# OpticalFlowExt.net
KiCad netlist of a schematic drawn in Altium Designer
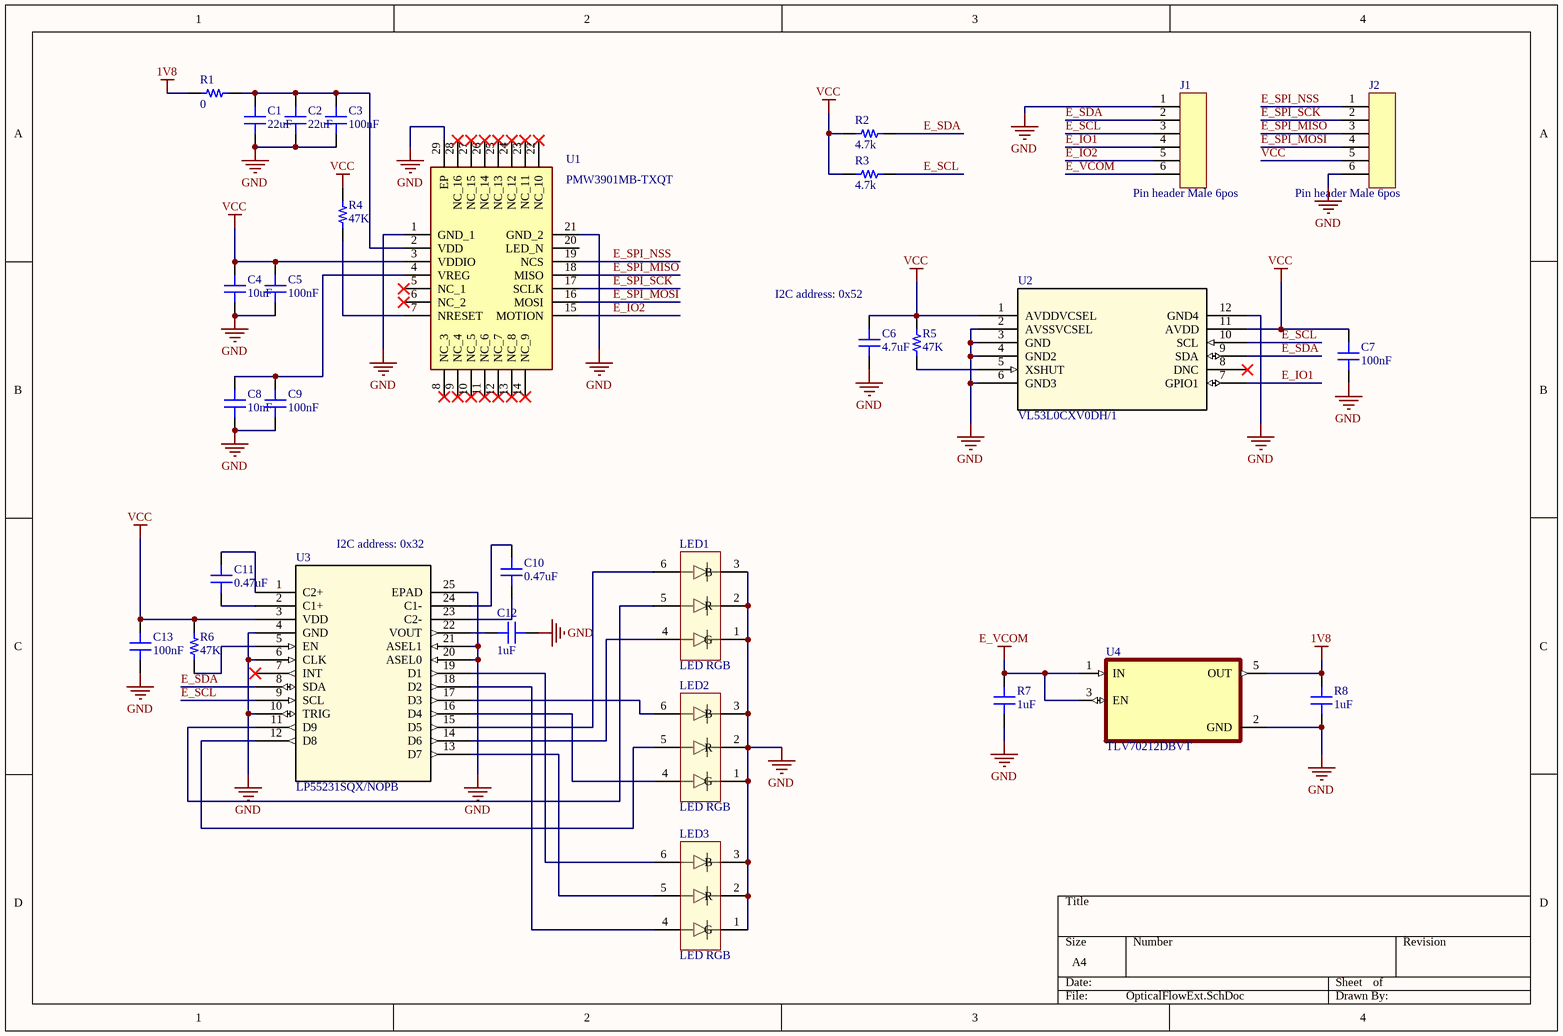
[diagram p0: OpticalFlowExt.SchDoc]

(export (version "E")
  (design (tool "Eeschema 10.0.6"))
  (components
    (comp (ref "C1")
      (value "22uF")
      (footprint "CAP 0402_1005")
      (description "CAP CER 150PF 50V NP0 0402")
      (fields (field (name "PART NUMBER") "C0402C151F5GAC7867") (field (name "MANUFACTURER") "KEMET"))
      (libsource (lib "Celestial Altium Library - altium_library") (part "Capacitor"))
    )
    (comp (ref "C2")
      (value "22uF")
      (footprint "CAP 0402_1005")
      (description "CAP CER 150PF 50V NP0 0402")
      (fields (field (name "PART NUMBER") "C0402C151F5GAC7867") (field (name "MANUFACTURER") "KEMET"))
      (libsource (lib "Celestial Altium Library - altium_library") (part "Capacitor"))
    )
    (comp (ref "C3")
      (value "100nF")
      (footprint "CAP 0402_1005")
      (description "CAP CER 150PF 50V NP0 0402")
      (fields (field (name "PART NUMBER") "C0402C151F5GAC7867") (field (name "MANUFACTURER") "KEMET"))
      (libsource (lib "Celestial Altium Library - altium_library") (part "Capacitor"))
    )
    (comp (ref "C4")
      (value "10uF")
      (footprint "CAP 0402_1005")
      (description "CAP CER 150PF 50V NP0 0402")
      (fields (field (name "PART NUMBER") "C0402C151F5GAC7867") (field (name "MANUFACTURER") "KEMET"))
      (libsource (lib "Celestial Altium Library - altium_library") (part "Capacitor"))
    )
    (comp (ref "C5")
      (value "100nF")
      (footprint "CAP 0402_1005")
      (description "CAP CER 150PF 50V NP0 0402")
      (fields (field (name "PART NUMBER") "C0402C151F5GAC7867") (field (name "MANUFACTURER") "KEMET"))
      (libsource (lib "Celestial Altium Library - altium_library") (part "Capacitor"))
    )
    (comp (ref "C6")
      (value "4.7uF")
      (footprint "CAP 0402_1005")
      (description "CAP CER 150PF 50V NP0 0402")
      (fields (field (name "PART NUMBER") "C0402C151F5GAC7867") (field (name "MANUFACTURER") "KEMET"))
      (libsource (lib "Celestial Altium Library - altium_library") (part "Capacitor"))
    )
    (comp (ref "C7")
      (value "100nF")
      (footprint "CAP 0402_1005")
      (description "CAP CER 150PF 50V NP0 0402")
      (fields (field (name "PART NUMBER") "C0402C151F5GAC7867") (field (name "MANUFACTURER") "KEMET"))
      (libsource (lib "Celestial Altium Library - altium_library") (part "Capacitor"))
    )
    (comp (ref "C8")
      (value "10nF")
      (footprint "CAP 0402_1005")
      (description "CAP CER 150PF 50V NP0 0402")
      (fields (field (name "PART NUMBER") "C0402C151F5GAC7867") (field (name "MANUFACTURER") "KEMET"))
      (libsource (lib "Celestial Altium Library - altium_library") (part "Capacitor"))
    )
    (comp (ref "C9")
      (value "100nF")
      (footprint "CAP 0402_1005")
      (description "CAP CER 150PF 50V NP0 0402")
      (fields (field (name "PART NUMBER") "C0402C151F5GAC7867") (field (name "MANUFACTURER") "KEMET"))
      (libsource (lib "Celestial Altium Library - altium_library") (part "Capacitor"))
    )
    (comp (ref "C10")
      (value "0.47uF")
      (footprint "CAP 0402_1005")
      (description "CAP CER 150PF 50V NP0 0402")
      (fields (field (name "PART NUMBER") "C0402C151F5GAC7867") (field (name "MANUFACTURER") "KEMET"))
      (libsource (lib "Celestial Altium Library - altium_library") (part "Capacitor"))
    )
    (comp (ref "C11")
      (value "0.47uF")
      (footprint "CAP 0402_1005")
      (description "CAP CER 150PF 50V NP0 0402")
      (fields (field (name "PART NUMBER") "C0402C151F5GAC7867") (field (name "MANUFACTURER") "KEMET"))
      (libsource (lib "Celestial Altium Library - altium_library") (part "Capacitor"))
    )
    (comp (ref "C12")
      (value "1uF")
      (footprint "CAP 0402_1005")
      (description "CAP CER 150PF 50V NP0 0402")
      (fields (field (name "PART NUMBER") "C0402C151F5GAC7867") (field (name "MANUFACTURER") "KEMET"))
      (libsource (lib "Celestial Altium Library - altium_library") (part "Capacitor"))
    )
    (comp (ref "C13")
      (value "100nF")
      (footprint "CAP 0402_1005")
      (description "CAP CER 150PF 50V NP0 0402")
      (fields (field (name "PART NUMBER") "C0402C151F5GAC7867") (field (name "MANUFACTURER") "KEMET"))
      (libsource (lib "Celestial Altium Library - altium_library") (part "Capacitor"))
    )
    (comp (ref "J1")
      (value "Pin header Male 6pos")
      (footprint "6 pin pads")
      (description "male pin header 6 pos")
      (libsource (lib "Schlib1") (part "Pin header Male 6pos"))
    )
    (comp (ref "J2")
      (value "Pin header Male 6pos")
      (footprint "6 pin pads")
      (description "male pin header 6 pos")
      (libsource (lib "Schlib1") (part "Pin header Male 6pos"))
    )
    (comp (ref "LED1")
      (value "LED RGB")
      (footprint "PCBComponent_1")
      (description "703-1039 element14")
      (libsource (lib "OpticalFlowExt") (part "LED RGB"))
    )
    (comp (ref "LED2")
      (value "LED RGB")
      (footprint "PCBComponent_1")
      (description "703-1039 element14")
      (libsource (lib "OpticalFlowExt") (part "LED RGB"))
    )
    (comp (ref "LED3")
      (value "LED RGB")
      (footprint "PCBComponent_1")
      (description "703-1039 element14")
      (libsource (lib "OpticalFlowExt") (part "LED RGB"))
    )
    (comp (ref "R1")
      (value "0")
      (footprint "RES 0402_1005")
      (description "RES SMD 47.5K OHM 1% 1/16W 0402")
      (fields (field (name "PART NUMBER") "RC0402FR-0747K5L") (field (name "MANUFACTURER") "Yageo"))
      (libsource (lib "Celestial Altium Library - altium_library") (part "Resistor"))
    )
    (comp (ref "R2")
      (value "4.7k")
      (footprint "RES 0402_1005")
      (description "RES SMD 47.5K OHM 1% 1/16W 0402")
      (fields (field (name "PART NUMBER") "RC0402FR-0747K5L") (field (name "MANUFACTURER") "Yageo"))
      (libsource (lib "Celestial Altium Library - altium_library") (part "Resistor"))
    )
    (comp (ref "R3")
      (value "4.7k")
      (footprint "RES 0402_1005")
      (description "RES SMD 47.5K OHM 1% 1/16W 0402")
      (fields (field (name "PART NUMBER") "RC0402FR-0747K5L") (field (name "MANUFACTURER") "Yageo"))
      (libsource (lib "Celestial Altium Library - altium_library") (part "Resistor"))
    )
    (comp (ref "R4")
      (value "47K")
      (footprint "RES 0402_1005")
      (description "RES SMD 47.5K OHM 1% 1/16W 0402")
      (fields (field (name "PART NUMBER") "RC0402FR-0747K5L") (field (name "MANUFACTURER") "Yageo"))
      (libsource (lib "Celestial Altium Library - altium_library") (part "Resistor"))
    )
    (comp (ref "R5")
      (value "47K")
      (footprint "RES 0402_1005")
      (description "RES SMD 47.5K OHM 1% 1/16W 0402")
      (fields (field (name "PART NUMBER") "RC0402FR-0747K5L") (field (name "MANUFACTURER") "Yageo"))
      (libsource (lib "Celestial Altium Library - altium_library") (part "Resistor"))
    )
    (comp (ref "R6")
      (value "47K")
      (footprint "RES 0402_1005")
      (description "RES SMD 47.5K OHM 1% 1/16W 0402")
      (fields (field (name "PART NUMBER") "RC0402FR-0747K5L") (field (name "MANUFACTURER") "Yageo"))
      (libsource (lib "Celestial Altium Library - altium_library") (part "Resistor"))
    )
    (comp (ref "R7")
      (value "1uF")
      (footprint "CAP 0402_1005")
      (description "CAP CER 150PF 50V NP0 0402")
      (fields (field (name "PART NUMBER") "C0402C151F5GAC7867") (field (name "MANUFACTURER") "KEMET"))
      (libsource (lib "Celestial Altium Library - altium_library") (part "Capacitor"))
    )
    (comp (ref "R8")
      (value "1uF")
      (footprint "CAP 0402_1005")
      (description "CAP CER 150PF 50V NP0 0402")
      (fields (field (name "PART NUMBER") "C0402C151F5GAC7867") (field (name "MANUFACTURER") "KEMET"))
      (libsource (lib "Celestial Altium Library - altium_library") (part "Capacitor"))
    )
    (comp (ref "U1")
      (value "PMW3901MB-TXQT")
      (footprint "SamacSys:PMW3901MBTXQT")
      (description "Integrated Circuit")
      (libsource (lib "*") (part "PMW3901MB-TXQT"))
    )
    (comp (ref "U2")
      (value "VL53L0CXV0DH/1")
      (footprint "LGA12_STM")
      (description "No Description Available")
      (fields (field (name "COPYRIGHT") "Copyright (C) 2018 Accelerated Designs. All rights reserved"))
      (libsource (lib "OpticalFlowExt") (part "VL53L0CXV0DH/1"))
    )
    (comp (ref "U3")
      (value "LP55231SQX/NOPB")
      (footprint "RTW24_TEX")
      (description "No Description Available")
      (fields (field (name "COPYRIGHT") "Copyright (C) 2018 Accelerated Designs. All rights reserved"))
      (libsource (lib "OpticalFlowExt") (part "LP55231SQX/NOPB"))
    )
    (comp (ref "U4")
      (value "TLV70212DBVT")
      (footprint "SOT95P280X145-5N")
      (description "300-mA, high-PSRR, low-IQ, low-dropout voltage regulator with enable 5-SOT-23 -40 to 125")
      (fields (field (name "MF") "Texas Instruments"))
      (libsource (lib "OpticalFlowExt") (part "LDO1.8"))
    )
  )
  (nets
    (net (code "1") (name "/E_IO1") (class "Default")
      (node (ref "J1") (pin "4") (pinfunction "4_4") (pintype "passive"))
      (node (ref "U2") (pin "7") (pinfunction "GPIO1_7") (pintype "bidirectional"))
    )
    (net (code "2") (name "/E_IO2") (class "Default")
      (node (ref "J1") (pin "5") (pinfunction "5_5") (pintype "passive"))
      (node (ref "U1") (pin "15") (pinfunction "MOTION_15") (pintype "passive"))
    )
    (net (code "3") (name "/E_SCL") (class "Default")
      (node (ref "J1") (pin "3") (pinfunction "3_3") (pintype "passive"))
      (node (ref "R3") (pin "1") (pinfunction "1_1") (pintype "passive"))
      (node (ref "U2") (pin "10") (pinfunction "SCL_10") (pintype "input"))
      (node (ref "U3") (pin "9") (pinfunction "SCL_9") (pintype "input"))
    )
    (net (code "4") (name "/E_SDA") (class "Default")
      (node (ref "J1") (pin "2") (pinfunction "2_2") (pintype "passive"))
      (node (ref "R2") (pin "1") (pinfunction "1_1") (pintype "passive"))
      (node (ref "U2") (pin "9") (pinfunction "SDA_9") (pintype "bidirectional"))
      (node (ref "U3") (pin "8") (pinfunction "SDA_8") (pintype "bidirectional"))
    )
    (net (code "5") (name "/E_SPI_MISO") (class "Default")
      (node (ref "J2") (pin "3") (pinfunction "3_3") (pintype "passive"))
      (node (ref "U1") (pin "18") (pinfunction "MISO_18") (pintype "passive"))
    )
    (net (code "6") (name "/E_SPI_MOSI") (class "Default")
      (node (ref "J2") (pin "4") (pinfunction "4_4") (pintype "passive"))
      (node (ref "U1") (pin "16") (pinfunction "MOSI_16") (pintype "passive"))
    )
    (net (code "7") (name "/E_SPI_NSS") (class "Default")
      (node (ref "J2") (pin "1") (pinfunction "1_1") (pintype "passive"))
      (node (ref "U1") (pin "19") (pinfunction "NCS_19") (pintype "passive"))
    )
    (net (code "8") (name "/E_SPI_SCK") (class "Default")
      (node (ref "J2") (pin "2") (pinfunction "2_2") (pintype "passive"))
      (node (ref "U1") (pin "17") (pinfunction "SCLK_17") (pintype "passive"))
    )
    (net (code "9") (name "1V8") (class "Default")
      (node (ref "R1") (pin "1") (pinfunction "1_1") (pintype "passive"))
      (node (ref "R8") (pin "2") (pinfunction "2_2") (pintype "passive"))
      (node (ref "U4") (pin "5") (pinfunction "OUT_5") (pintype "output"))
    )
    (net (code "10") (name "E_VCOM") (class "Default")
      (node (ref "J1") (pin "6") (pinfunction "6_6") (pintype "passive"))
      (node (ref "R7") (pin "2") (pinfunction "2_2") (pintype "passive"))
      (node (ref "U4") (pin "1") (pinfunction "IN_1") (pintype "input"))
      (node (ref "U4") (pin "3") (pinfunction "EN_3") (pintype "bidirectional"))
    )
    (net (code "11") (name "GND") (class "Default")
      (node (ref "C1") (pin "1") (pinfunction "1_1") (pintype "passive"))
      (node (ref "C12") (pin "1") (pinfunction "1_1") (pintype "passive"))
      (node (ref "C13") (pin "1") (pinfunction "1_1") (pintype "passive"))
      (node (ref "C2") (pin "1") (pinfunction "1_1") (pintype "passive"))
      (node (ref "C3") (pin "1") (pinfunction "1_1") (pintype "passive"))
      (node (ref "C4") (pin "1") (pinfunction "1_1") (pintype "passive"))
      (node (ref "C5") (pin "1") (pinfunction "1_1") (pintype "passive"))
      (node (ref "C6") (pin "1") (pinfunction "1_1") (pintype "passive"))
      (node (ref "C7") (pin "1") (pinfunction "1_1") (pintype "passive"))
      (node (ref "C8") (pin "1") (pinfunction "1_1") (pintype "passive"))
      (node (ref "C9") (pin "1") (pinfunction "1_1") (pintype "passive"))
      (node (ref "J1") (pin "1") (pinfunction "1_1") (pintype "passive"))
      (node (ref "J2") (pin "6") (pinfunction "6_6") (pintype "passive"))
      (node (ref "LED1") (pin "1") (pinfunction "G_1") (pintype "passive"))
      (node (ref "LED1") (pin "2") (pinfunction "R_2") (pintype "passive"))
      (node (ref "LED1") (pin "3") (pinfunction "B_3") (pintype "passive"))
      (node (ref "LED2") (pin "1") (pinfunction "G_1") (pintype "passive"))
      (node (ref "LED2") (pin "2") (pinfunction "R_2") (pintype "passive"))
      (node (ref "LED2") (pin "3") (pinfunction "B_3") (pintype "passive"))
      (node (ref "LED3") (pin "1") (pinfunction "G_1") (pintype "passive"))
      (node (ref "LED3") (pin "2") (pinfunction "R_2") (pintype "passive"))
      (node (ref "LED3") (pin "3") (pinfunction "B_3") (pintype "passive"))
      (node (ref "R7") (pin "1") (pinfunction "1_1") (pintype "passive"))
      (node (ref "R8") (pin "1") (pinfunction "1_1") (pintype "passive"))
      (node (ref "U1") (pin "1") (pinfunction "GND_1_1") (pintype "passive"))
      (node (ref "U1") (pin "21") (pinfunction "GND_2_21") (pintype "passive"))
      (node (ref "U1") (pin "29") (pinfunction "EP_29") (pintype "passive"))
      (node (ref "U2") (pin "12") (pinfunction "GND4_12") (pintype "power_in"))
      (node (ref "U2") (pin "2") (pinfunction "AVSSVCSEL_2") (pintype "power_in"))
      (node (ref "U2") (pin "3") (pinfunction "GND_3") (pintype "power_in"))
      (node (ref "U2") (pin "4") (pinfunction "GND2_4") (pintype "power_in"))
      (node (ref "U2") (pin "6") (pinfunction "GND3_6") (pintype "power_in"))
      (node (ref "U3") (pin "10") (pinfunction "TRIG_10") (pintype "bidirectional"))
      (node (ref "U3") (pin "20") (pinfunction "ASEL0_20") (pintype "input"))
      (node (ref "U3") (pin "21") (pinfunction "ASEL1_21") (pintype "input"))
      (node (ref "U3") (pin "25") (pinfunction "EPAD_25") (pintype "passive"))
      (node (ref "U3") (pin "4") (pinfunction "GND_4") (pintype "power_in"))
      (node (ref "U3") (pin "6") (pinfunction "CLK_6") (pintype "input"))
      (node (ref "U4") (pin "2") (pinfunction "GND_2") (pintype "power_in"))
    )
    (net (code "12") (name "Net-(U1-NRESET)") (class "Default")
      (node (ref "R4") (pin "1") (pinfunction "1_1") (pintype "passive"))
      (node (ref "U1") (pin "7") (pinfunction "NRESET_7") (pintype "passive"))
    )
    (net (code "13") (name "Net-(U1-VDD)") (class "Default")
      (node (ref "C1") (pin "2") (pinfunction "2_2") (pintype "passive"))
      (node (ref "C2") (pin "2") (pinfunction "2_2") (pintype "passive"))
      (node (ref "C3") (pin "2") (pinfunction "2_2") (pintype "passive"))
      (node (ref "R1") (pin "2") (pinfunction "2_2") (pintype "passive"))
      (node (ref "U1") (pin "2") (pinfunction "VDD_2") (pintype "passive"))
    )
    (net (code "14") (name "Net-(U1-VREG)") (class "Default")
      (node (ref "C8") (pin "2") (pinfunction "2_2") (pintype "passive"))
      (node (ref "C9") (pin "2") (pinfunction "2_2") (pintype "passive"))
      (node (ref "U1") (pin "4") (pinfunction "VREG_4") (pintype "passive"))
    )
    (net (code "15") (name "Net-(U2-XSHUT)") (class "Default")
      (node (ref "R5") (pin "1") (pinfunction "1_1") (pintype "passive"))
      (node (ref "U2") (pin "5") (pinfunction "XSHUT_5") (pintype "input"))
    )
    (net (code "16") (name "Net-(U3-C1+)") (class "Default")
      (node (ref "C11") (pin "1") (pinfunction "1_1") (pintype "passive"))
      (node (ref "U3") (pin "2") (pinfunction "C1+_2") (pintype "passive"))
    )
    (net (code "17") (name "Net-(U3-C1-)") (class "Default")
      (node (ref "C10") (pin "2") (pinfunction "2_2") (pintype "passive"))
      (node (ref "U3") (pin "24") (pinfunction "C1-_24") (pintype "passive"))
    )
    (net (code "18") (name "Net-(U3-C2+)") (class "Default")
      (node (ref "C11") (pin "2") (pinfunction "2_2") (pintype "passive"))
      (node (ref "U3") (pin "1") (pinfunction "C2+_1") (pintype "passive"))
    )
    (net (code "19") (name "Net-(U3-C2-)") (class "Default")
      (node (ref "C10") (pin "1") (pinfunction "1_1") (pintype "passive"))
      (node (ref "U3") (pin "23") (pinfunction "C2-_23") (pintype "passive"))
    )
    (net (code "20") (name "Net-(U3-D1)") (class "Default")
      (node (ref "LED3") (pin "6") (pintype "passive"))
      (node (ref "U3") (pin "19") (pinfunction "D1_19") (pintype "output"))
    )
    (net (code "21") (name "Net-(U3-D2)") (class "Default")
      (node (ref "LED3") (pin "4") (pintype "passive"))
      (node (ref "U3") (pin "18") (pinfunction "D2_18") (pintype "output"))
    )
    (net (code "22") (name "Net-(U3-D3)") (class "Default")
      (node (ref "LED2") (pin "6") (pintype "passive"))
      (node (ref "U3") (pin "17") (pinfunction "D3_17") (pintype "output"))
    )
    (net (code "23") (name "Net-(U3-D4)") (class "Default")
      (node (ref "LED2") (pin "4") (pintype "passive"))
      (node (ref "U3") (pin "16") (pinfunction "D4_16") (pintype "output"))
    )
    (net (code "24") (name "Net-(U3-D5)") (class "Default")
      (node (ref "LED1") (pin "6") (pintype "passive"))
      (node (ref "U3") (pin "15") (pinfunction "D5_15") (pintype "output"))
    )
    (net (code "25") (name "Net-(U3-D6)") (class "Default")
      (node (ref "LED1") (pin "4") (pintype "passive"))
      (node (ref "U3") (pin "14") (pinfunction "D6_14") (pintype "output"))
    )
    (net (code "26") (name "Net-(U3-D7)") (class "Default")
      (node (ref "LED3") (pin "5") (pintype "passive"))
      (node (ref "U3") (pin "13") (pinfunction "D7_13") (pintype "output"))
    )
    (net (code "27") (name "Net-(U3-D8)") (class "Default")
      (node (ref "LED2") (pin "5") (pintype "passive"))
      (node (ref "U3") (pin "12") (pinfunction "D8_12") (pintype "output"))
    )
    (net (code "28") (name "Net-(U3-D9)") (class "Default")
      (node (ref "LED1") (pin "5") (pintype "passive"))
      (node (ref "U3") (pin "11") (pinfunction "D9_11") (pintype "output"))
    )
    (net (code "29") (name "Net-(U3-EN)") (class "Default")
      (node (ref "R6") (pin "1") (pinfunction "1_1") (pintype "passive"))
      (node (ref "U3") (pin "5") (pinfunction "EN_5") (pintype "input"))
    )
    (net (code "30") (name "Net-(U3-VOUT)") (class "Default")
      (node (ref "C12") (pin "2") (pinfunction "2_2") (pintype "passive"))
      (node (ref "U3") (pin "22") (pinfunction "VOUT_22") (pintype "output"))
    )
    (net (code "31") (name "VCC") (class "Default")
      (node (ref "C13") (pin "2") (pinfunction "2_2") (pintype "passive"))
      (node (ref "C4") (pin "2") (pinfunction "2_2") (pintype "passive"))
      (node (ref "C5") (pin "2") (pinfunction "2_2") (pintype "passive"))
      (node (ref "C6") (pin "2") (pinfunction "2_2") (pintype "passive"))
      (node (ref "C7") (pin "2") (pinfunction "2_2") (pintype "passive"))
      (node (ref "J2") (pin "5") (pinfunction "5_5") (pintype "passive"))
      (node (ref "R2") (pin "2") (pinfunction "2_2") (pintype "passive"))
      (node (ref "R3") (pin "2") (pinfunction "2_2") (pintype "passive"))
      (node (ref "R4") (pin "2") (pinfunction "2_2") (pintype "passive"))
      (node (ref "R5") (pin "2") (pinfunction "2_2") (pintype "passive"))
      (node (ref "R6") (pin "2") (pinfunction "2_2") (pintype "passive"))
      (node (ref "U1") (pin "3") (pinfunction "VDDIO_3") (pintype "passive"))
      (node (ref "U2") (pin "1") (pinfunction "AVDDVCSEL_1") (pintype "power_in"))
      (node (ref "U2") (pin "11") (pinfunction "AVDD_11") (pintype "power_in"))
      (node (ref "U3") (pin "3") (pinfunction "VDD_3") (pintype "power_in"))
    )
    (net (code "32") (name "unconnected-(U1-LED_N-Pad20)") (class "Default")
      (node (ref "U1") (pin "20") (pinfunction "LED_N_20") (pintype "passive"))
    )
    (net (code "33") (name "unconnected-(U1-NC_1-Pad5)") (class "Default")
      (node (ref "U1") (pin "5") (pinfunction "NC_1_5") (pintype "passive+no_connect"))
    )
    (net (code "34") (name "unconnected-(U1-NC_2-Pad6)") (class "Default")
      (node (ref "U1") (pin "6") (pinfunction "NC_2_6") (pintype "passive+no_connect"))
    )
    (net (code "35") (name "unconnected-(U1-NC_3-Pad8)") (class "Default")
      (node (ref "U1") (pin "8") (pinfunction "NC_3_8") (pintype "passive+no_connect"))
    )
    (net (code "36") (name "unconnected-(U1-NC_4-Pad9)") (class "Default")
      (node (ref "U1") (pin "9") (pinfunction "NC_4_9") (pintype "passive+no_connect"))
    )
    (net (code "37") (name "unconnected-(U1-NC_5-Pad10)") (class "Default")
      (node (ref "U1") (pin "10") (pinfunction "NC_5_10") (pintype "passive+no_connect"))
    )
    (net (code "38") (name "unconnected-(U1-NC_6-Pad11)") (class "Default")
      (node (ref "U1") (pin "11") (pinfunction "NC_6_11") (pintype "passive+no_connect"))
    )
    (net (code "39") (name "unconnected-(U1-NC_7-Pad12)") (class "Default")
      (node (ref "U1") (pin "12") (pinfunction "NC_7_12") (pintype "passive+no_connect"))
    )
    (net (code "40") (name "unconnected-(U1-NC_8-Pad13)") (class "Default")
      (node (ref "U1") (pin "13") (pinfunction "NC_8_13") (pintype "passive+no_connect"))
    )
    (net (code "41") (name "unconnected-(U1-NC_9-Pad14)") (class "Default")
      (node (ref "U1") (pin "14") (pinfunction "NC_9_14") (pintype "passive+no_connect"))
    )
    (net (code "42") (name "unconnected-(U1-NC_10-Pad22)") (class "Default")
      (node (ref "U1") (pin "22") (pinfunction "NC_10_22") (pintype "passive+no_connect"))
    )
    (net (code "43") (name "unconnected-(U1-NC_11-Pad23)") (class "Default")
      (node (ref "U1") (pin "23") (pinfunction "NC_11_23") (pintype "passive+no_connect"))
    )
    (net (code "44") (name "unconnected-(U1-NC_12-Pad24)") (class "Default")
      (node (ref "U1") (pin "24") (pinfunction "NC_12_24") (pintype "passive+no_connect"))
    )
    (net (code "45") (name "unconnected-(U1-NC_13-Pad25)") (class "Default")
      (node (ref "U1") (pin "25") (pinfunction "NC_13_25") (pintype "passive+no_connect"))
    )
    (net (code "46") (name "unconnected-(U1-NC_14-Pad26)") (class "Default")
      (node (ref "U1") (pin "26") (pinfunction "NC_14_26") (pintype "passive+no_connect"))
    )
    (net (code "47") (name "unconnected-(U1-NC_15-Pad27)") (class "Default")
      (node (ref "U1") (pin "27") (pinfunction "NC_15_27") (pintype "passive+no_connect"))
    )
    (net (code "48") (name "unconnected-(U1-NC_16-Pad28)") (class "Default")
      (node (ref "U1") (pin "28") (pinfunction "NC_16_28") (pintype "passive+no_connect"))
    )
    (net (code "49") (name "unconnected-(U2-DNC-Pad8)") (class "Default")
      (node (ref "U2") (pin "8") (pinfunction "DNC_8") (pintype "passive+no_connect"))
    )
    (net (code "50") (name "unconnected-(U3-INT-Pad7)") (class "Default")
      (node (ref "U3") (pin "7") (pinfunction "INT_7") (pintype "output+no_connect"))
    )
  )
)
